# design.net
KiCad netlist of a schematic drawn in Altium Designer
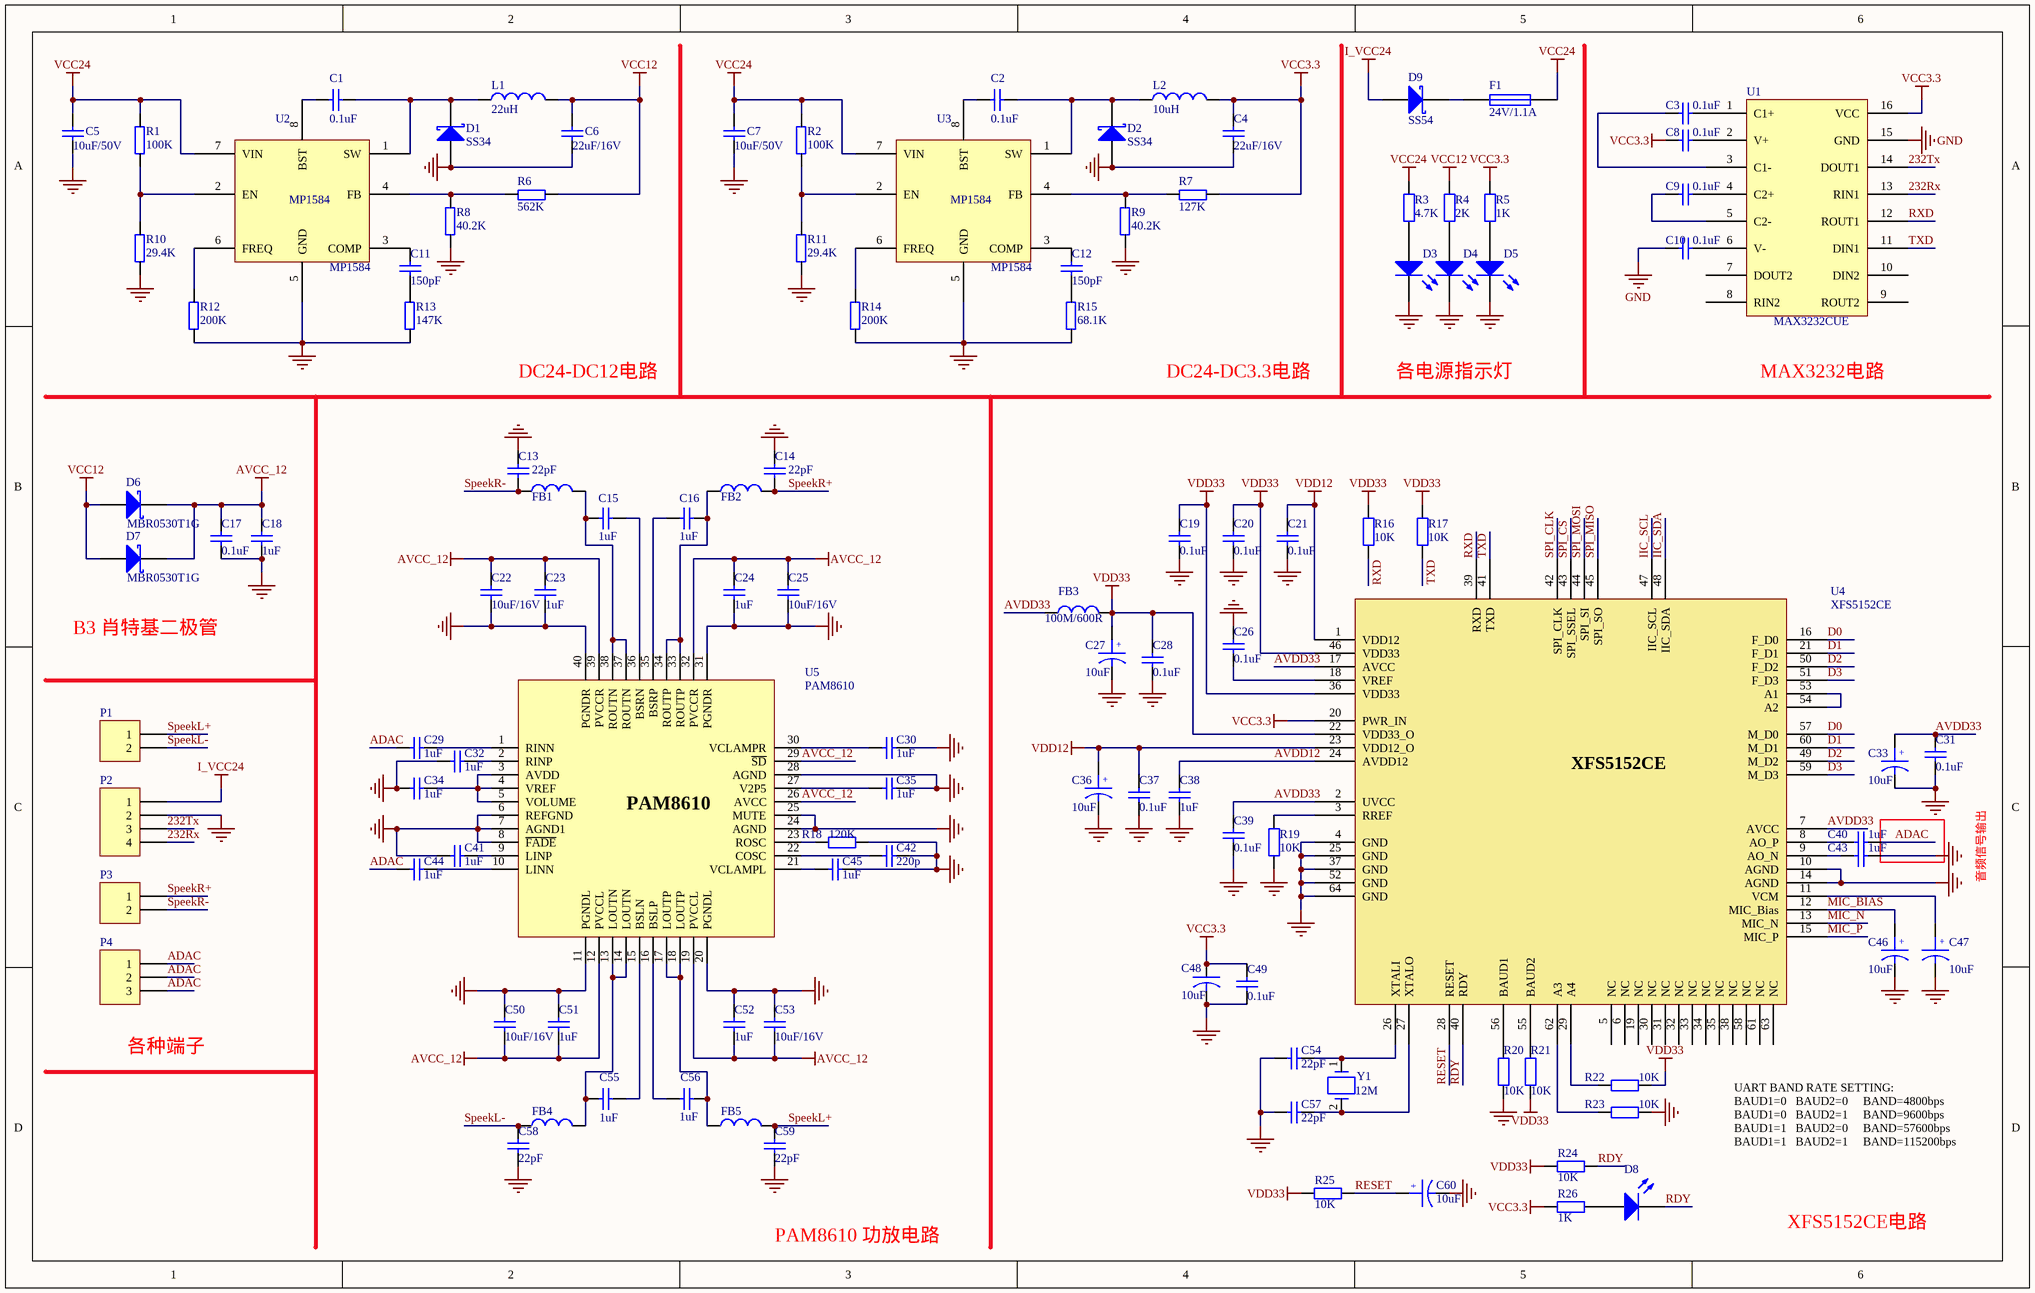
[diagram p0: 盟科大讯飞.SchDoc]

(export (version "E")
  (design (tool "Eeschema 10.0.6"))
  (components
    (comp (ref "C1")
      (value "0.1uF")
      (footprint "LC-0603_C")
      (description "Capacitor (Semiconductor SIM Model)")
      (fields (field (name "PUBLISHER") "Altium Limited"))
      (libsource (lib "Miscellaneous Devices") (part "Cap Semi"))
    )
    (comp (ref "C2")
      (value "0.1uF")
      (footprint "LC-0603_C")
      (description "Capacitor (Semiconductor SIM Model)")
      (fields (field (name "PUBLISHER") "Altium Limited"))
      (libsource (lib "Miscellaneous Devices") (part "Cap Semi"))
    )
    (comp (ref "C3")
      (value "0.1uF")
      (footprint "LC-0603_C")
      (description "Capacitor (Semiconductor SIM Model)")
      (fields (field (name "PUBLISHER") "Altium Limited"))
      (libsource (lib "Miscellaneous Devices") (part "Cap Semi"))
    )
    (comp (ref "C4")
      (value "22uF/16V")
      (footprint "LC-1206_C")
      (description "Capacitor (Semiconductor SIM Model)")
      (fields (field (name "PUBLISHER") "Altium Limited"))
      (libsource (lib "Miscellaneous Devices") (part "Cap Semi"))
    )
    (comp (ref "C5")
      (value "10uF/50V")
      (footprint "LC-1206_C")
      (description "Capacitor (Semiconductor SIM Model)")
      (fields (field (name "PUBLISHER") "Altium Limited"))
      (libsource (lib "Miscellaneous Devices") (part "Cap Semi"))
    )
    (comp (ref "C6")
      (value "22uF/16V")
      (footprint "LC-1206_C")
      (description "Capacitor (Semiconductor SIM Model)")
      (fields (field (name "PUBLISHER") "Altium Limited"))
      (libsource (lib "Miscellaneous Devices") (part "Cap Semi"))
    )
    (comp (ref "C7")
      (value "10uF/50V")
      (footprint "LC-1206_C")
      (description "Capacitor (Semiconductor SIM Model)")
      (fields (field (name "PUBLISHER") "Altium Limited"))
      (libsource (lib "Miscellaneous Devices") (part "Cap Semi"))
    )
    (comp (ref "C8")
      (value "0.1uF")
      (footprint "LC-0603_C")
      (description "Capacitor (Semiconductor SIM Model)")
      (fields (field (name "PUBLISHER") "Altium Limited"))
      (libsource (lib "Miscellaneous Devices") (part "Cap Semi"))
    )
    (comp (ref "C9")
      (value "0.1uF")
      (footprint "LC-0603_C")
      (description "Capacitor (Semiconductor SIM Model)")
      (fields (field (name "PUBLISHER") "Altium Limited"))
      (libsource (lib "Miscellaneous Devices") (part "Cap Semi"))
    )
    (comp (ref "C10")
      (value "0.1uF")
      (footprint "LC-0603_C")
      (description "Capacitor (Semiconductor SIM Model)")
      (fields (field (name "PUBLISHER") "Altium Limited"))
      (libsource (lib "Miscellaneous Devices") (part "Cap Semi"))
    )
    (comp (ref "C11")
      (value "150pF")
      (footprint "LC-0603_C")
      (description "Capacitor (Semiconductor SIM Model)")
      (fields (field (name "PUBLISHER") "Altium Limited"))
      (libsource (lib "Miscellaneous Devices") (part "Cap Semi"))
    )
    (comp (ref "C12")
      (value "150pF")
      (footprint "LC-0603_C")
      (description "Capacitor (Semiconductor SIM Model)")
      (fields (field (name "PUBLISHER") "Altium Limited"))
      (libsource (lib "Miscellaneous Devices") (part "Cap Semi"))
    )
    (comp (ref "C13")
      (value "22pF")
      (footprint "LC-0603_C")
      (description "Capacitor (Semiconductor SIM Model)")
      (fields (field (name "PUBLISHER") "Altium Limited"))
      (libsource (lib "Miscellaneous Devices") (part "Cap Semi"))
    )
    (comp (ref "C14")
      (value "22pF")
      (footprint "LC-0603_C")
      (description "Capacitor (Semiconductor SIM Model)")
      (fields (field (name "PUBLISHER") "Altium Limited"))
      (libsource (lib "Miscellaneous Devices") (part "Cap Semi"))
    )
    (comp (ref "C15")
      (value "1uF")
      (footprint "LC-0603_C")
      (description "Capacitor (Semiconductor SIM Model)")
      (fields (field (name "PUBLISHER") "Altium Limited"))
      (libsource (lib "Miscellaneous Devices") (part "Cap Semi"))
    )
    (comp (ref "C16")
      (value "1uF")
      (footprint "LC-0603_C")
      (description "Capacitor (Semiconductor SIM Model)")
      (fields (field (name "PUBLISHER") "Altium Limited"))
      (libsource (lib "Miscellaneous Devices") (part "Cap Semi"))
    )
    (comp (ref "C17")
      (value "0.1uF")
      (footprint "LC-0603_C")
      (description "Capacitor (Semiconductor SIM Model)")
      (fields (field (name "PUBLISHER") "Altium Limited"))
      (libsource (lib "Miscellaneous Devices") (part "Cap Semi"))
    )
    (comp (ref "C18")
      (value "1uF")
      (footprint "LC-0603_C")
      (description "Capacitor (Semiconductor SIM Model)")
      (fields (field (name "PUBLISHER") "Altium Limited"))
      (libsource (lib "Miscellaneous Devices") (part "Cap Semi"))
    )
    (comp (ref "C19")
      (value "0.1uF")
      (footprint "LC-0603_C")
      (description "Capacitor (Semiconductor SIM Model)")
      (fields (field (name "PUBLISHER") "Altium Limited"))
      (libsource (lib "Miscellaneous Devices") (part "Cap Semi"))
    )
    (comp (ref "C20")
      (value "0.1uF")
      (footprint "LC-0603_C")
      (description "Capacitor (Semiconductor SIM Model)")
      (fields (field (name "PUBLISHER") "Altium Limited"))
      (libsource (lib "Miscellaneous Devices") (part "Cap Semi"))
    )
    (comp (ref "C21")
      (value "0.1uF")
      (footprint "LC-0603_C")
      (description "Capacitor (Semiconductor SIM Model)")
      (fields (field (name "PUBLISHER") "Altium Limited"))
      (libsource (lib "Miscellaneous Devices") (part "Cap Semi"))
    )
    (comp (ref "C22")
      (value "10uF/16V")
      (footprint "LC-1206_C")
      (description "电容")
      (fields (field (name "PUBLISHER") "Altium Limited"))
      (libsource (lib "*") (part "Cap NP"))
    )
    (comp (ref "C23")
      (value "1uF")
      (footprint "LC-0603_C")
      (description "Capacitor (Semiconductor SIM Model)")
      (fields (field (name "PUBLISHER") "Altium Limited"))
      (libsource (lib "Miscellaneous Devices") (part "Cap Semi"))
    )
    (comp (ref "C24")
      (value "1uF")
      (footprint "LC-0603_C")
      (description "Capacitor (Semiconductor SIM Model)")
      (fields (field (name "PUBLISHER") "Altium Limited"))
      (libsource (lib "Miscellaneous Devices") (part "Cap Semi"))
    )
    (comp (ref "C25")
      (value "10uF/16V")
      (footprint "LC-1206_C")
      (description "电容")
      (fields (field (name "PUBLISHER") "Altium Limited"))
      (libsource (lib "*") (part "Cap NP"))
    )
    (comp (ref "C26")
      (value "0.1uF")
      (footprint "LC-0603_C")
      (description "Capacitor (Semiconductor SIM Model)")
      (fields (field (name "PUBLISHER") "Altium Limited"))
      (libsource (lib "Miscellaneous Devices") (part "Cap Semi"))
    )
    (comp (ref "C27") (value "10uF") (footprint "LC-CASE-A_3216") (libsource (lib "*") (part "CAP POL")))
    (comp (ref "C28")
      (value "0.1uF")
      (footprint "LC-0603_C")
      (description "Capacitor (Semiconductor SIM Model)")
      (fields (field (name "PUBLISHER") "Altium Limited"))
      (libsource (lib "Miscellaneous Devices") (part "Cap Semi"))
    )
    (comp (ref "C29")
      (value "1uF")
      (footprint "LC-0603_C")
      (description "Capacitor (Semiconductor SIM Model)")
      (fields (field (name "PUBLISHER") "Altium Limited"))
      (libsource (lib "Miscellaneous Devices") (part "Cap Semi"))
    )
    (comp (ref "C30")
      (value "1uF")
      (footprint "LC-0603_C")
      (description "Capacitor (Semiconductor SIM Model)")
      (fields (field (name "PUBLISHER") "Altium Limited"))
      (libsource (lib "Miscellaneous Devices") (part "Cap Semi"))
    )
    (comp (ref "C31")
      (value "0.1uF")
      (footprint "LC-0603_C")
      (description "Capacitor (Semiconductor SIM Model)")
      (fields (field (name "PUBLISHER") "Altium Limited"))
      (libsource (lib "Miscellaneous Devices") (part "Cap Semi"))
    )
    (comp (ref "C32")
      (value "1uF")
      (footprint "LC-0603_C")
      (description "Capacitor (Semiconductor SIM Model)")
      (fields (field (name "PUBLISHER") "Altium Limited"))
      (libsource (lib "Miscellaneous Devices") (part "Cap Semi"))
    )
    (comp (ref "C33") (value "10uF") (footprint "LC-CASE-A_3216") (libsource (lib "*") (part "CAP POL")))
    (comp (ref "C34")
      (value "1uF")
      (footprint "LC-0603_C")
      (description "Capacitor (Semiconductor SIM Model)")
      (fields (field (name "PUBLISHER") "Altium Limited"))
      (libsource (lib "Miscellaneous Devices") (part "Cap Semi"))
    )
    (comp (ref "C35")
      (value "1uF")
      (footprint "LC-0603_C")
      (description "Capacitor (Semiconductor SIM Model)")
      (fields (field (name "PUBLISHER") "Altium Limited"))
      (libsource (lib "Miscellaneous Devices") (part "Cap Semi"))
    )
    (comp (ref "C36") (value "10uF") (footprint "LC-CASE-A_3216") (libsource (lib "*") (part "CAP POL")))
    (comp (ref "C37")
      (value "0.1uF")
      (footprint "LC-0603_C")
      (description "Capacitor (Semiconductor SIM Model)")
      (fields (field (name "PUBLISHER") "Altium Limited"))
      (libsource (lib "Miscellaneous Devices") (part "Cap Semi"))
    )
    (comp (ref "C38")
      (value "1uF")
      (footprint "LC-0603_C")
      (description "Capacitor (Semiconductor SIM Model)")
      (fields (field (name "PUBLISHER") "Altium Limited"))
      (libsource (lib "Miscellaneous Devices") (part "Cap Semi"))
    )
    (comp (ref "C39")
      (value "0.1uF")
      (footprint "LC-0603_C")
      (description "Capacitor (Semiconductor SIM Model)")
      (fields (field (name "PUBLISHER") "Altium Limited"))
      (libsource (lib "Miscellaneous Devices") (part "Cap Semi"))
    )
    (comp (ref "C40")
      (value "1uF")
      (footprint "LC-0603_C")
      (description "Capacitor (Semiconductor SIM Model)")
      (fields (field (name "PUBLISHER") "Altium Limited"))
      (libsource (lib "Miscellaneous Devices") (part "Cap Semi"))
    )
    (comp (ref "C41")
      (value "1uF")
      (footprint "LC-0603_C")
      (description "Capacitor (Semiconductor SIM Model)")
      (fields (field (name "PUBLISHER") "Altium Limited"))
      (libsource (lib "Miscellaneous Devices") (part "Cap Semi"))
    )
    (comp (ref "C42")
      (value "220p")
      (footprint "LC-0603_C")
      (description "Capacitor (Semiconductor SIM Model)")
      (fields (field (name "PUBLISHER") "Altium Limited"))
      (libsource (lib "Miscellaneous Devices") (part "Cap Semi"))
    )
    (comp (ref "C43")
      (value "1uF")
      (footprint "LC-0603_C")
      (description "Capacitor (Semiconductor SIM Model)")
      (fields (field (name "PUBLISHER") "Altium Limited"))
      (libsource (lib "Miscellaneous Devices") (part "Cap Semi"))
    )
    (comp (ref "C44")
      (value "1uF")
      (footprint "LC-0603_C")
      (description "Capacitor (Semiconductor SIM Model)")
      (fields (field (name "PUBLISHER") "Altium Limited"))
      (libsource (lib "Miscellaneous Devices") (part "Cap Semi"))
    )
    (comp (ref "C45")
      (value "1uF")
      (footprint "LC-0603_C")
      (description "Capacitor (Semiconductor SIM Model)")
      (fields (field (name "PUBLISHER") "Altium Limited"))
      (libsource (lib "Miscellaneous Devices") (part "Cap Semi"))
    )
    (comp (ref "C46") (value "10uF") (footprint "LC-CASE-A_3216") (libsource (lib "*") (part "CAP POL")))
    (comp (ref "C47") (value "10uF") (footprint "LC-CASE-A_3216") (libsource (lib "*") (part "CAP POL")))
    (comp (ref "C48")
      (value "10uF")
      (footprint "LC-CASE-A_3216")
      (description "Capacitor")
      (libsource (lib "*") (part "CAPACITOR"))
    )
    (comp (ref "C49")
      (value "0.1uF")
      (footprint "LC-0603_C")
      (description "Capacitor (Semiconductor SIM Model)")
      (fields (field (name "PUBLISHER") "Altium Limited"))
      (libsource (lib "Miscellaneous Devices") (part "Cap Semi"))
    )
    (comp (ref "C50")
      (value "10uF/16V")
      (footprint "LC-1206_C")
      (description "电容")
      (fields (field (name "PUBLISHER") "Altium Limited"))
      (libsource (lib "*") (part "Cap NP"))
    )
    (comp (ref "C51")
      (value "1uF")
      (footprint "LC-0603_C")
      (description "Capacitor (Semiconductor SIM Model)")
      (fields (field (name "PUBLISHER") "Altium Limited"))
      (libsource (lib "Miscellaneous Devices") (part "Cap Semi"))
    )
    (comp (ref "C52")
      (value "1uF")
      (footprint "LC-0603_C")
      (description "Capacitor (Semiconductor SIM Model)")
      (fields (field (name "PUBLISHER") "Altium Limited"))
      (libsource (lib "Miscellaneous Devices") (part "Cap Semi"))
    )
    (comp (ref "C53")
      (value "10uF/16V")
      (footprint "LC-1206_C")
      (description "电容")
      (fields (field (name "PUBLISHER") "Altium Limited"))
      (libsource (lib "*") (part "Cap NP"))
    )
    (comp (ref "C54")
      (value "22pF")
      (footprint "LC-0603_C")
      (description "电容")
      (fields (field (name "PUBLISHER") "Altium Limited"))
      (libsource (lib "*") (part "Cap NP"))
    )
    (comp (ref "C55")
      (value "1uF")
      (footprint "LC-0603_C")
      (description "Capacitor (Semiconductor SIM Model)")
      (fields (field (name "PUBLISHER") "Altium Limited"))
      (libsource (lib "Miscellaneous Devices") (part "Cap Semi"))
    )
    (comp (ref "C56")
      (value "1uF")
      (footprint "LC-0603_C")
      (description "Capacitor (Semiconductor SIM Model)")
      (fields (field (name "PUBLISHER") "Altium Limited"))
      (libsource (lib "Miscellaneous Devices") (part "Cap Semi"))
    )
    (comp (ref "C57")
      (value "22pF")
      (footprint "LC-0603_C")
      (description "电容")
      (fields (field (name "PUBLISHER") "Altium Limited"))
      (libsource (lib "*") (part "Cap NP"))
    )
    (comp (ref "C58")
      (value "22pF")
      (footprint "LC-0603_C")
      (description "Capacitor (Semiconductor SIM Model)")
      (fields (field (name "PUBLISHER") "Altium Limited"))
      (libsource (lib "Miscellaneous Devices") (part "Cap Semi"))
    )
    (comp (ref "C59")
      (value "22pF")
      (footprint "LC-0603_C")
      (description "Capacitor (Semiconductor SIM Model)")
      (fields (field (name "PUBLISHER") "Altium Limited"))
      (libsource (lib "Miscellaneous Devices") (part "Cap Semi"))
    )
    (comp (ref "C60") (value "10uF") (footprint "LC-CASE-A_3216") (libsource (lib "*") (part "CAP POL")))
    (comp (ref "D1")
      (value "SS34")
      (footprint "SS34")
      (description "Schottky Rectifier")
      (fields (field (name "PUBLISHER") "Altium Limited"))
      (libsource (lib "Miscellaneous Devices") (part "Diode 18TQ045"))
    )
    (comp (ref "D2")
      (value "SS34")
      (footprint "SS34")
      (description "Schottky Rectifier")
      (fields (field (name "PUBLISHER") "Altium Limited"))
      (libsource (lib "Miscellaneous Devices") (part "Diode 18TQ045"))
    )
    (comp (ref "D3")
      (value "LED")
      (footprint "LC-0805_LED_S1")
      (description "Typical INFRARED GaAs LED")
      (fields (field (name "PUBLISHER") "Altium Limited"))
      (libsource (lib "Miscellaneous Devices") (part "LED0"))
    )
    (comp (ref "D4")
      (value "LED")
      (footprint "LC-0805_LED_S1")
      (description "Typical INFRARED GaAs LED")
      (fields (field (name "PUBLISHER") "Altium Limited"))
      (libsource (lib "Miscellaneous Devices") (part "LED0"))
    )
    (comp (ref "D5")
      (value "LED")
      (footprint "LC-0805_LED_S1")
      (description "Typical INFRARED GaAs LED")
      (fields (field (name "PUBLISHER") "Altium Limited"))
      (libsource (lib "Miscellaneous Devices") (part "LED0"))
    )
    (comp (ref "D6")
      (value "MBR0530T1G")
      (footprint "B3肖特基二极管")
      (description "Schottky Rectifier")
      (fields (field (name "PUBLISHER") "Altium Limited"))
      (libsource (lib "Miscellaneous Devices") (part "Diode 18TQ045"))
    )
    (comp (ref "D7")
      (value "MBR0530T1G")
      (footprint "B3肖特基二极管")
      (description "Schottky Rectifier")
      (fields (field (name "PUBLISHER") "Altium Limited"))
      (libsource (lib "Miscellaneous Devices") (part "Diode 18TQ045"))
    )
    (comp (ref "D8")
      (value "LED")
      (footprint "LC-0805_LED_S1")
      (description "Typical INFRARED GaAs LED")
      (fields (field (name "PUBLISHER") "Altium Limited"))
      (libsource (lib "Miscellaneous Devices") (part "LED0"))
    )
    (comp (ref "D9")
      (value "SS54")
      (footprint "DIOM6959X26N")
      (description "Schottky Rectifier")
      (fields (field (name "PUBLISHER") "Altium Limited"))
      (libsource (lib "Miscellaneous Devices") (part "Diode 18TQ045"))
    )
    (comp (ref "F1")
      (value "24V/1.1A")
      (footprint "1206 F")
      (description "Fuse")
      (fields (field (name "PUBLISHER") "Altium Limited"))
      (libsource (lib "Miscellaneous Devices") (part "Fuse 1"))
    )
    (comp (ref "FB1")
      (value "100M/600R")
      (footprint "LC-0805_L")
      (description "磁珠")
      (fields (field (name "PUBLISHER") "Altium Limited"))
      (libsource (lib "*") (part "Fbead"))
    )
    (comp (ref "FB2")
      (value "100M/600R")
      (footprint "LC-0805_L")
      (description "磁珠")
      (fields (field (name "PUBLISHER") "Altium Limited"))
      (libsource (lib "*") (part "Fbead"))
    )
    (comp (ref "FB3")
      (value "100M/600R")
      (footprint "LC-0805_L")
      (description "磁珠")
      (fields (field (name "PUBLISHER") "Altium Limited"))
      (libsource (lib "*") (part "Fbead"))
    )
    (comp (ref "FB4")
      (value "100M/600R")
      (footprint "LC-0805_L")
      (description "磁珠")
      (fields (field (name "PUBLISHER") "Altium Limited"))
      (libsource (lib "*") (part "Fbead"))
    )
    (comp (ref "FB5")
      (value "100M/600R")
      (footprint "LC-0805_L")
      (description "磁珠")
      (fields (field (name "PUBLISHER") "Altium Limited"))
      (libsource (lib "*") (part "Fbead"))
    )
    (comp (ref "L1")
      (value "22uH")
      (footprint "7*7*4mm电感")
      (description "Inductor")
      (fields (field (name "PUBLISHER") "Altium Limited"))
      (libsource (lib "Miscellaneous Devices") (part "Inductor"))
    )
    (comp (ref "L2")
      (value "10uH")
      (footprint "7*7*4mm电感")
      (description "Inductor")
      (fields (field (name "PUBLISHER") "Altium Limited"))
      (libsource (lib "Miscellaneous Devices") (part "Inductor"))
    )
    (comp (ref "P1")
      (value "~")
      (footprint "DZ-2-3.5mm")
      (description "Header, 2-Pin")
      (fields (field (name "PUBLISHER") "Altium Limited"))
      (libsource (lib "Miscellaneous Connectors") (part "Header 2"))
    )
    (comp (ref "P2")
      (value "~")
      (footprint "DZ-4-3.5mm")
      (description "Header, 4-Pin")
      (fields (field (name "PUBLISHER") "Altium Limited"))
      (libsource (lib "Miscellaneous Connectors") (part "Header 4"))
    )
    (comp (ref "P3")
      (value "~")
      (footprint "DZ-2-3.5mm")
      (description "Header, 2-Pin")
      (fields (field (name "PUBLISHER") "Altium Limited"))
      (libsource (lib "Miscellaneous Connectors") (part "Header 2"))
    )
    (comp (ref "P4")
      (value "~")
      (footprint "单刀双掷贴片开关")
      (description "Header, 3-Pin")
      (fields (field (name "PUBLISHER") "Altium Limited"))
      (libsource (lib "Miscellaneous Connectors") (part "Header 3"))
    )
    (comp (ref "R1")
      (value "100K")
      (footprint "LC-0603_R")
      (libsource (lib "Explorer STM32F407封装库") (part "R_2"))
    )
    (comp (ref "R2")
      (value "100K")
      (footprint "LC-0603_R")
      (libsource (lib "Explorer STM32F407封装库") (part "R_2"))
    )
    (comp (ref "R3")
      (value "4.7K")
      (footprint "LC-0603_R")
      (description "Resistor")
      (fields (field (name "PUBLISHER") "Altium Limited"))
      (libsource (lib "*") (part "Res2"))
    )
    (comp (ref "R4")
      (value "2K")
      (footprint "LC-0603_R")
      (description "Resistor")
      (fields (field (name "PUBLISHER") "Altium Limited"))
      (libsource (lib "") (part "Res2_3"))
    )
    (comp (ref "R5")
      (value "1K")
      (footprint "LC-0603_R")
      (description "Resistor")
      (fields (field (name "PUBLISHER") "Altium Limited"))
      (libsource (lib "*") (part "Res2"))
    )
    (comp (ref "R6")
      (value "562K")
      (footprint "LC-0603_R")
      (libsource (lib "Explorer STM32F407封装库") (part "R_2"))
    )
    (comp (ref "R7")
      (value "127K")
      (footprint "LC-0603_R")
      (libsource (lib "Explorer STM32F407封装库") (part "R_2"))
    )
    (comp (ref "R8")
      (value "40.2K")
      (footprint "LC-0603_R")
      (libsource (lib "Explorer STM32F407封装库") (part "R_2"))
    )
    (comp (ref "R9")
      (value "40.2K")
      (footprint "LC-0603_R")
      (libsource (lib "Explorer STM32F407封装库") (part "R_2"))
    )
    (comp (ref "R10")
      (value "29.4K")
      (footprint "LC-0603_R")
      (libsource (lib "Explorer STM32F407封装库") (part "R_2"))
    )
    (comp (ref "R11")
      (value "29.4K")
      (footprint "LC-0603_R")
      (libsource (lib "Explorer STM32F407封装库") (part "R_2"))
    )
    (comp (ref "R12")
      (value "200K")
      (footprint "LC-0603_R")
      (libsource (lib "Explorer STM32F407封装库") (part "R_2"))
    )
    (comp (ref "R13")
      (value "147K")
      (footprint "LC-0603_R")
      (libsource (lib "Explorer STM32F407封装库") (part "R_2"))
    )
    (comp (ref "R14")
      (value "200K")
      (footprint "LC-0603_R")
      (libsource (lib "Explorer STM32F407封装库") (part "R_2"))
    )
    (comp (ref "R15")
      (value "68.1K")
      (footprint "LC-0603_R")
      (libsource (lib "Explorer STM32F407封装库") (part "R_2"))
    )
    (comp (ref "R16")
      (value "10K")
      (footprint "LC-0603_R")
      (description "Resistor")
      (fields (field (name "PUBLISHER") "Altium Limited"))
      (libsource (lib "") (part "Res2_3"))
    )
    (comp (ref "R17")
      (value "10K")
      (footprint "LC-0603_R")
      (description "Resistor")
      (fields (field (name "PUBLISHER") "Altium Limited"))
      (libsource (lib "*") (part "Res2"))
    )
    (comp (ref "R18")
      (value "120K")
      (footprint "LC-0603_R")
      (description "Resistor")
      (fields (field (name "PUBLISHER") "Altium Limited"))
      (libsource (lib "") (part "Res2_2"))
    )
    (comp (ref "R19")
      (value "10K")
      (footprint "LC-0603_R")
      (description "Resistor")
      (fields (field (name "PUBLISHER") "Altium Limited"))
      (libsource (lib "") (part "Res2_3"))
    )
    (comp (ref "R20")
      (value "10K")
      (footprint "LC-0603_R")
      (description "Resistor")
      (fields (field (name "PUBLISHER") "Altium Limited"))
      (libsource (lib "*") (part "Res2"))
    )
    (comp (ref "R21")
      (value "10K")
      (footprint "LC-0603_R")
      (description "Resistor")
      (fields (field (name "PUBLISHER") "Altium Limited"))
      (libsource (lib "*") (part "Res2"))
    )
    (comp (ref "R22")
      (value "10K")
      (footprint "LC-0603_R")
      (description "Resistor")
      (fields (field (name "PUBLISHER") "Altium Limited"))
      (libsource (lib "") (part "Res2_1"))
    )
    (comp (ref "R23")
      (value "10K")
      (footprint "LC-0603_R")
      (description "Resistor")
      (fields (field (name "PUBLISHER") "Altium Limited"))
      (libsource (lib "") (part "Res2_2"))
    )
    (comp (ref "R24")
      (value "10K")
      (footprint "LC-0603_R")
      (description "Resistor")
      (fields (field (name "PUBLISHER") "Altium Limited"))
      (libsource (lib "") (part "Res2_1"))
    )
    (comp (ref "R25")
      (value "10K")
      (footprint "LC-0603_R")
      (description "Resistor")
      (fields (field (name "PUBLISHER") "Altium Limited"))
      (libsource (lib "") (part "Res2_1"))
    )
    (comp (ref "R26")
      (value "1K")
      (footprint "LC-0603_R")
      (description "Resistor")
      (fields (field (name "PUBLISHER") "Altium Limited"))
      (libsource (lib "") (part "Res2_1"))
    )
    (comp (ref "U1")
      (value "MAX3232CUE")
      (footprint "LC-SOIC-16_150mil")
      (libsource (lib "Smart_board_v1") (part "MAX3232CUE"))
    )
    (comp (ref "U2")
      (value "MP1584")
      (footprint "LC-SOIC-8_EP_150mil")
      (libsource (lib "磁导航") (part "MP1584EN"))
    )
    (comp (ref "U3")
      (value "MP1584")
      (footprint "LC-SOIC-8_EP_150mil")
      (libsource (lib "磁导航") (part "MP1584EN"))
    )
    (comp (ref "U4") (value "XFS5152CE") (footprint "LQFP64 10*10") (libsource (lib "*") (part "XFS5152-2")))
    (comp (ref "U5")
      (value "PAM8610")
      (footprint "QFN50P600X600X80-40N")
      (libsource (lib "my third") (part "PAM8610功放芯片"))
    )
    (comp (ref "Y1")
      (value "12M")
      (footprint "XTAL 晶振")
      (description "晶振")
      (libsource (lib "*") (part "XTAL1"))
    )
  )
  (nets
    (net (code "1") (name "/232Rx") (class "Default")
      (node (ref "P2") (pin "4") (pinfunction "4_4") (pintype "passive"))
      (node (ref "U1") (pin "13") (pinfunction "RIN1_13") (pintype "passive"))
    )
    (net (code "2") (name "/232Tx") (class "Default")
      (node (ref "P2") (pin "3") (pinfunction "3_3") (pintype "passive"))
      (node (ref "U1") (pin "14") (pinfunction "DOUT1_14") (pintype "passive"))
    )
    (net (code "3") (name "/ADAC") (class "Default")
      (node (ref "C29") (pin "1") (pinfunction "1_1") (pintype "passive"))
      (node (ref "C40") (pin "1") (pinfunction "1_1") (pintype "passive"))
      (node (ref "C44") (pin "1") (pinfunction "1_1") (pintype "passive"))
      (node (ref "P4") (pin "1") (pinfunction "1_1") (pintype "passive"))
      (node (ref "P4") (pin "2") (pinfunction "2_2") (pintype "passive"))
      (node (ref "P4") (pin "3") (pinfunction "3_3") (pintype "passive"))
    )
    (net (code "4") (name "/AVDD12") (class "Default")
      (node (ref "C38") (pin "2") (pinfunction "2_2") (pintype "passive"))
      (node (ref "U4") (pin "24") (pinfunction "AVDD12_24") (pintype "passive"))
    )
    (net (code "5") (name "/AVDD33") (class "Default")
      (node (ref "C31") (pin "1") (pinfunction "1_1") (pintype "passive"))
      (node (ref "C33") (pin "1") (pinfunction "1_1") (pintype "passive"))
      (node (ref "C39") (pin "1") (pinfunction "1_1") (pintype "passive"))
      (node (ref "FB3") (pin "1") (pinfunction "1_1") (pintype "passive"))
      (node (ref "U4") (pin "17") (pinfunction "AVCC_17") (pintype "passive"))
      (node (ref "U4") (pin "2") (pinfunction "UVCC_2") (pintype "passive"))
      (node (ref "U4") (pin "7") (pinfunction "AVCC_7") (pintype "passive"))
    )
    (net (code "6") (name "/D0") (class "Default")
      (node (ref "U4") (pin "16") (pinfunction "F_D0_16") (pintype "passive"))
      (node (ref "U4") (pin "57") (pinfunction "M_D0_57") (pintype "passive"))
    )
    (net (code "7") (name "/D1") (class "Default")
      (node (ref "U4") (pin "21") (pinfunction "F_D1_21") (pintype "passive"))
      (node (ref "U4") (pin "60") (pinfunction "M_D1_60") (pintype "passive"))
    )
    (net (code "8") (name "/D2") (class "Default")
      (node (ref "U4") (pin "49") (pinfunction "M_D2_49") (pintype "passive"))
      (node (ref "U4") (pin "50") (pinfunction "F_D2_50") (pintype "passive"))
    )
    (net (code "9") (name "/D3") (class "Default")
      (node (ref "U4") (pin "51") (pinfunction "F_D3_51") (pintype "passive"))
      (node (ref "U4") (pin "59") (pinfunction "M_D3_59") (pintype "passive"))
    )
    (net (code "10") (name "/IIC_SCL") (class "Default")
      (node (ref "U4") (pin "47") (pinfunction "IIC_SCL_47") (pintype "passive"))
    )
    (net (code "11") (name "/IIC_SDA") (class "Default")
      (node (ref "U4") (pin "48") (pinfunction "IIC_SDA_48") (pintype "passive"))
    )
    (net (code "12") (name "/MIC_BIAS") (class "Default")
      (node (ref "C46") (pin "1") (pinfunction "1_1") (pintype "passive"))
      (node (ref "U4") (pin "12") (pinfunction "MIC_Bias_12") (pintype "passive"))
    )
    (net (code "13") (name "/MIC_N") (class "Default")
      (node (ref "U4") (pin "13") (pinfunction "MIC_N_13") (pintype "passive"))
    )
    (net (code "14") (name "/MIC_P") (class "Default")
      (node (ref "U4") (pin "15") (pinfunction "MIC_P_15") (pintype "passive"))
    )
    (net (code "15") (name "/RDY") (class "Default")
      (node (ref "D8") (pin "2") (pinfunction "K_2") (pintype "passive"))
      (node (ref "R24") (pin "2") (pinfunction "2_2") (pintype "passive"))
      (node (ref "U4") (pin "40") (pinfunction "RDY_40") (pintype "passive"))
    )
    (net (code "16") (name "/RESET") (class "Default")
      (node (ref "C60") (pin "1") (pinfunction "1_1") (pintype "passive"))
      (node (ref "R25") (pin "2") (pinfunction "2_2") (pintype "passive"))
      (node (ref "U4") (pin "28") (pinfunction "RESET_28") (pintype "passive"))
    )
    (net (code "17") (name "/RXD") (class "Default")
      (node (ref "R16") (pin "1") (pinfunction "1_1") (pintype "passive"))
      (node (ref "U1") (pin "12") (pinfunction "ROUT1_12") (pintype "passive"))
      (node (ref "U4") (pin "39") (pinfunction "RXD_39") (pintype "passive"))
    )
    (net (code "18") (name "/SPI_CLK") (class "Default")
      (node (ref "U4") (pin "42") (pinfunction "SPI_CLK_42") (pintype "passive"))
    )
    (net (code "19") (name "/SPI_CS") (class "Default")
      (node (ref "U4") (pin "43") (pinfunction "SPI_SSEL_43") (pintype "passive"))
    )
    (net (code "20") (name "/SPI_MISO") (class "Default")
      (node (ref "U4") (pin "45") (pinfunction "SPI_SO_45") (pintype "passive"))
    )
    (net (code "21") (name "/SPI_MOSI") (class "Default")
      (node (ref "U4") (pin "44") (pinfunction "SPI_SI_44") (pintype "passive"))
    )
    (net (code "22") (name "/SpeekL+") (class "Default")
      (node (ref "C59") (pin "2") (pinfunction "2_2") (pintype "passive"))
      (node (ref "FB5") (pin "2") (pinfunction "2_2") (pintype "passive"))
      (node (ref "P1") (pin "1") (pinfunction "1_1") (pintype "passive"))
    )
    (net (code "23") (name "/SpeekL-") (class "Default")
      (node (ref "C58") (pin "2") (pinfunction "2_2") (pintype "passive"))
      (node (ref "FB4") (pin "1") (pinfunction "1_1") (pintype "passive"))
      (node (ref "P1") (pin "2") (pinfunction "2_2") (pintype "passive"))
    )
    (net (code "24") (name "/SpeekR+") (class "Default")
      (node (ref "C14") (pin "2") (pinfunction "2_2") (pintype "passive"))
      (node (ref "FB2") (pin "2") (pinfunction "2_2") (pintype "passive"))
      (node (ref "P3") (pin "1") (pinfunction "1_1") (pintype "passive"))
    )
    (net (code "25") (name "/SpeekR-") (class "Default")
      (node (ref "C13") (pin "2") (pinfunction "2_2") (pintype "passive"))
      (node (ref "FB1") (pin "1") (pinfunction "1_1") (pintype "passive"))
      (node (ref "P3") (pin "2") (pinfunction "2_2") (pintype "passive"))
    )
    (net (code "26") (name "/TXD") (class "Default")
      (node (ref "R17") (pin "2") (pinfunction "2_2") (pintype "passive"))
      (node (ref "U1") (pin "11") (pinfunction "DIN1_11") (pintype "passive"))
      (node (ref "U4") (pin "41") (pinfunction "TXD_41") (pintype "passive"))
    )
    (net (code "27") (name "AVCC_12") (class "Default")
      (node (ref "C17") (pin "1") (pinfunction "1_1") (pintype "passive"))
      (node (ref "C18") (pin "1") (pinfunction "1_1") (pintype "passive"))
      (node (ref "C22") (pin "1") (pinfunction "1_1") (pintype "passive"))
      (node (ref "C23") (pin "1") (pinfunction "1_1") (pintype "passive"))
      (node (ref "C24") (pin "1") (pinfunction "1_1") (pintype "passive"))
      (node (ref "C25") (pin "1") (pinfunction "1_1") (pintype "passive"))
      (node (ref "C50") (pin "1") (pinfunction "1_1") (pintype "passive"))
      (node (ref "C51") (pin "1") (pinfunction "1_1") (pintype "passive"))
      (node (ref "C52") (pin "1") (pinfunction "1_1") (pintype "passive"))
      (node (ref "C53") (pin "1") (pinfunction "1_1") (pintype "passive"))
      (node (ref "D6") (pin "1") (pinfunction "K_1") (pintype "passive"))
      (node (ref "D7") (pin "1") (pinfunction "K_1") (pintype "passive"))
      (node (ref "U5") (pin "12") (pinfunction "PVCCL_12") (pintype "passive"))
      (node (ref "U5") (pin "19") (pinfunction "PVCCL_19") (pintype "passive"))
      (node (ref "U5") (pin "26") (pinfunction "AVCC_26") (pintype "passive"))
      (node (ref "U5") (pin "29") (pinfunction "~{SD}_29") (pintype "passive"))
      (node (ref "U5") (pin "32") (pinfunction "PVCCR_32") (pintype "passive"))
      (node (ref "U5") (pin "39") (pinfunction "PVCCR_39") (pintype "passive"))
    )
    (net (code "28") (name "GND") (class "Default")
      (node (ref "C10") (pin "2") (pinfunction "2_2") (pintype "passive"))
      (node (ref "C13") (pin "1") (pinfunction "1_1") (pintype "passive"))
      (node (ref "C14") (pin "1") (pinfunction "1_1") (pintype "passive"))
      (node (ref "C17") (pin "2") (pinfunction "2_2") (pintype "passive"))
      (node (ref "C18") (pin "2") (pinfunction "2_2") (pintype "passive"))
      (node (ref "C19") (pin "2") (pinfunction "2_2") (pintype "passive"))
      (node (ref "C20") (pin "2") (pinfunction "2_2") (pintype "passive"))
      (node (ref "C21") (pin "2") (pinfunction "2_2") (pintype "passive"))
      (node (ref "C22") (pin "2") (pinfunction "2_2") (pintype "passive"))
      (node (ref "C23") (pin "2") (pinfunction "2_2") (pintype "passive"))
      (node (ref "C24") (pin "2") (pinfunction "2_2") (pintype "passive"))
      (node (ref "C25") (pin "2") (pinfunction "2_2") (pintype "passive"))
      (node (ref "C26") (pin "1") (pinfunction "1_1") (pintype "passive"))
      (node (ref "C27") (pin "2") (pinfunction "2_2") (pintype "passive"))
      (node (ref "C28") (pin "2") (pinfunction "2_2") (pintype "passive"))
      (node (ref "C30") (pin "2") (pinfunction "2_2") (pintype "passive"))
      (node (ref "C31") (pin "2") (pinfunction "2_2") (pintype "passive"))
      (node (ref "C32") (pin "1") (pinfunction "1_1") (pintype "passive"))
      (node (ref "C33") (pin "2") (pinfunction "2_2") (pintype "passive"))
      (node (ref "C34") (pin "1") (pinfunction "1_1") (pintype "passive"))
      (node (ref "C35") (pin "2") (pinfunction "2_2") (pintype "passive"))
      (node (ref "C36") (pin "2") (pinfunction "2_2") (pintype "passive"))
      (node (ref "C37") (pin "2") (pinfunction "2_2") (pintype "passive"))
      (node (ref "C38") (pin "1") (pinfunction "1_1") (pintype "passive"))
      (node (ref "C39") (pin "2") (pinfunction "2_2") (pintype "passive"))
      (node (ref "C4") (pin "1") (pinfunction "1_1") (pintype "passive"))
      (node (ref "C41") (pin "1") (pinfunction "1_1") (pintype "passive"))
      (node (ref "C42") (pin "2") (pinfunction "2_2") (pintype "passive"))
      (node (ref "C43") (pin "1") (pinfunction "1_1") (pintype "passive"))
      (node (ref "C45") (pin "2") (pinfunction "2_2") (pintype "passive"))
      (node (ref "C46") (pin "2") (pinfunction "2_2") (pintype "passive"))
      (node (ref "C47") (pin "2") (pinfunction "2_2") (pintype "passive"))
      (node (ref "C48") (pin "2") (pinfunction "2_2") (pintype "passive"))
      (node (ref "C49") (pin "2") (pinfunction "2_2") (pintype "passive"))
      (node (ref "C5") (pin "2") (pinfunction "2_2") (pintype "passive"))
      (node (ref "C50") (pin "2") (pinfunction "2_2") (pintype "passive"))
      (node (ref "C51") (pin "2") (pinfunction "2_2") (pintype "passive"))
      (node (ref "C52") (pin "2") (pinfunction "2_2") (pintype "passive"))
      (node (ref "C53") (pin "2") (pinfunction "2_2") (pintype "passive"))
      (node (ref "C54") (pin "1") (pinfunction "1_1") (pintype "passive"))
      (node (ref "C57") (pin "1") (pinfunction "1_1") (pintype "passive"))
      (node (ref "C58") (pin "1") (pinfunction "1_1") (pintype "passive"))
      (node (ref "C59") (pin "1") (pinfunction "1_1") (pintype "passive"))
      (node (ref "C6") (pin "1") (pinfunction "1_1") (pintype "passive"))
      (node (ref "C60") (pin "2") (pinfunction "2_2") (pintype "passive"))
      (node (ref "C7") (pin "2") (pinfunction "2_2") (pintype "passive"))
      (node (ref "D1") (pin "2") (pinfunction "A_2") (pintype "passive"))
      (node (ref "D2") (pin "2") (pinfunction "A_2") (pintype "passive"))
      (node (ref "D3") (pin "2") (pinfunction "K_2") (pintype "passive"))
      (node (ref "D4") (pin "2") (pinfunction "K_2") (pintype "passive"))
      (node (ref "D5") (pin "2") (pinfunction "K_2") (pintype "passive"))
      (node (ref "P2") (pin "2") (pinfunction "2_2") (pintype "passive"))
      (node (ref "R10") (pin "2") (pintype "passive"))
      (node (ref "R11") (pin "2") (pintype "passive"))
      (node (ref "R12") (pin "2") (pintype "passive"))
      (node (ref "R13") (pin "2") (pintype "passive"))
      (node (ref "R14") (pin "2") (pintype "passive"))
      (node (ref "R15") (pin "2") (pintype "passive"))
      (node (ref "R18") (pin "1") (pinfunction "1_1") (pintype "passive"))
      (node (ref "R19") (pin "1") (pinfunction "1_1") (pintype "passive"))
      (node (ref "R20") (pin "2") (pinfunction "2_2") (pintype "passive"))
      (node (ref "R23") (pin "1") (pinfunction "1_1") (pintype "passive"))
      (node (ref "R8") (pin "2") (pintype "passive"))
      (node (ref "R9") (pin "2") (pintype "passive"))
      (node (ref "U1") (pin "15") (pinfunction "GND_15") (pintype "passive"))
      (node (ref "U2") (pin "5") (pinfunction "GND_5") (pintype "passive"))
      (node (ref "U3") (pin "5") (pinfunction "GND_5") (pintype "passive"))
      (node (ref "U4") (pin "10") (pinfunction "AGND_10") (pintype "passive"))
      (node (ref "U4") (pin "14") (pinfunction "AGND_14") (pintype "passive"))
      (node (ref "U4") (pin "25") (pinfunction "GND_25") (pintype "passive"))
      (node (ref "U4") (pin "37") (pinfunction "GND_37") (pintype "passive"))
      (node (ref "U4") (pin "4") (pinfunction "GND_4") (pintype "passive"))
      (node (ref "U4") (pin "52") (pinfunction "GND_52") (pintype "passive"))
      (node (ref "U4") (pin "64") (pinfunction "GND_64") (pintype "passive"))
      (node (ref "U5") (pin "11") (pinfunction "PGNDL_11") (pintype "passive"))
      (node (ref "U5") (pin "20") (pinfunction "PGNDL_20") (pintype "passive"))
      (node (ref "U5") (pin "24") (pinfunction "AGND_24") (pintype "passive"))
      (node (ref "U5") (pin "25") (pinfunction "MUTE_25") (pintype "passive"))
      (node (ref "U5") (pin "28") (pinfunction "AGND_28") (pintype "passive"))
      (node (ref "U5") (pin "31") (pinfunction "PGNDR_31") (pintype "passive"))
      (node (ref "U5") (pin "40") (pinfunction "PGNDR_40") (pintype "passive"))
      (node (ref "U5") (pin "6") (pinfunction "REFGND_6") (pintype "passive"))
      (node (ref "U5") (pin "7") (pinfunction "AGND1_7") (pintype "passive"))
      (node (ref "U5") (pin "8") (pinfunction "~{FADE}_8") (pintype "passive"))
    )
    (net (code "29") (name "I_VCC24") (class "Default")
      (node (ref "D9") (pin "2") (pinfunction "A_2") (pintype "passive"))
      (node (ref "P2") (pin "1") (pinfunction "1_1") (pintype "passive"))
    )
    (net (code "30") (name "Net-(C11-Pad1)") (class "Default")
      (node (ref "C11") (pin "1") (pinfunction "1_1") (pintype "passive"))
      (node (ref "R13") (pin "1") (pintype "passive"))
    )
    (net (code "31") (name "Net-(C12-Pad1)") (class "Default")
      (node (ref "C12") (pin "1") (pinfunction "1_1") (pintype "passive"))
      (node (ref "R15") (pin "1") (pintype "passive"))
    )
    (net (code "32") (name "Net-(C15-Pad1)") (class "Default")
      (node (ref "C15") (pin "1") (pinfunction "1_1") (pintype "passive"))
      (node (ref "FB1") (pin "2") (pinfunction "2_2") (pintype "passive"))
      (node (ref "U5") (pin "37") (pinfunction "ROUTN_37") (pintype "passive"))
      (node (ref "U5") (pin "38") (pinfunction "ROUTN_38") (pintype "passive"))
    )
    (net (code "33") (name "Net-(C16-Pad2)") (class "Default")
      (node (ref "C16") (pin "2") (pinfunction "2_2") (pintype "passive"))
      (node (ref "FB2") (pin "1") (pinfunction "1_1") (pintype "passive"))
      (node (ref "U5") (pin "33") (pinfunction "ROUTP_33") (pintype "passive"))
      (node (ref "U5") (pin "34") (pinfunction "ROUTP_34") (pintype "passive"))
    )
    (net (code "34") (name "Net-(C55-Pad2)") (class "Default")
      (node (ref "C55") (pin "2") (pinfunction "2_2") (pintype "passive"))
      (node (ref "FB4") (pin "2") (pinfunction "2_2") (pintype "passive"))
      (node (ref "U5") (pin "13") (pinfunction "LOUTN_13") (pintype "passive"))
      (node (ref "U5") (pin "14") (pinfunction "LOUTN_14") (pintype "passive"))
    )
    (net (code "35") (name "Net-(C56-Pad2)") (class "Default")
      (node (ref "C56") (pin "2") (pinfunction "2_2") (pintype "passive"))
      (node (ref "FB5") (pin "1") (pinfunction "1_1") (pintype "passive"))
      (node (ref "U5") (pin "17") (pinfunction "LOUTP_17") (pintype "passive"))
      (node (ref "U5") (pin "18") (pinfunction "LOUTP_18") (pintype "passive"))
    )
    (net (code "36") (name "Net-(D1-K)") (class "Default")
      (node (ref "C1") (pin "1") (pinfunction "1_1") (pintype "passive"))
      (node (ref "D1") (pin "1") (pinfunction "K_1") (pintype "passive"))
      (node (ref "L1") (pin "1") (pinfunction "1_1") (pintype "passive"))
      (node (ref "U2") (pin "1") (pinfunction "SW_1") (pintype "passive"))
    )
    (net (code "37") (name "Net-(D2-K)") (class "Default")
      (node (ref "C2") (pin "1") (pinfunction "1_1") (pintype "passive"))
      (node (ref "D2") (pin "1") (pinfunction "K_1") (pintype "passive"))
      (node (ref "L2") (pin "1") (pinfunction "1_1") (pintype "passive"))
      (node (ref "U3") (pin "1") (pinfunction "SW_1") (pintype "passive"))
    )
    (net (code "38") (name "Net-(D3-A)") (class "Default")
      (node (ref "D3") (pin "1") (pinfunction "A_1") (pintype "passive"))
      (node (ref "R3") (pin "2") (pinfunction "2_2") (pintype "passive"))
    )
    (net (code "39") (name "Net-(D4-A)") (class "Default")
      (node (ref "D4") (pin "1") (pinfunction "A_1") (pintype "passive"))
      (node (ref "R4") (pin "1") (pinfunction "1_1") (pintype "passive"))
    )
    (net (code "40") (name "Net-(D5-A)") (class "Default")
      (node (ref "D5") (pin "1") (pinfunction "A_1") (pintype "passive"))
      (node (ref "R5") (pin "2") (pinfunction "2_2") (pintype "passive"))
    )
    (net (code "41") (name "Net-(D8-A)") (class "Default")
      (node (ref "D8") (pin "1") (pinfunction "A_1") (pintype "passive"))
      (node (ref "R26") (pin "2") (pinfunction "2_2") (pintype "passive"))
    )
    (net (code "42") (name "Net-(D9-K)") (class "Default")
      (node (ref "D9") (pin "1") (pinfunction "K_1") (pintype "passive"))
      (node (ref "F1") (pin "1") (pinfunction "1_1") (pintype "passive"))
    )
    (net (code "43") (name "Net-(U1-C1+)") (class "Default")
      (node (ref "C3") (pin "1") (pinfunction "1_1") (pintype "passive"))
      (node (ref "U1") (pin "1") (pinfunction "C1+_1") (pintype "passive"))
    )
    (net (code "44") (name "Net-(U1-C1-)") (class "Default")
      (node (ref "C3") (pin "2") (pinfunction "2_2") (pintype "passive"))
      (node (ref "U1") (pin "3") (pinfunction "C1-_3") (pintype "passive"))
    )
    (net (code "45") (name "Net-(U1-C2+)") (class "Default")
      (node (ref "C9") (pin "1") (pinfunction "1_1") (pintype "passive"))
      (node (ref "U1") (pin "4") (pinfunction "C2+_4") (pintype "passive"))
    )
    (net (code "46") (name "Net-(U1-C2-)") (class "Default")
      (node (ref "C9") (pin "2") (pinfunction "2_2") (pintype "passive"))
      (node (ref "U1") (pin "5") (pinfunction "C2-_5") (pintype "passive"))
    )
    (net (code "47") (name "Net-(U1-V+)") (class "Default")
      (node (ref "C8") (pin "1") (pinfunction "1_1") (pintype "passive"))
      (node (ref "U1") (pin "2") (pinfunction "V+_2") (pintype "passive"))
    )
    (net (code "48") (name "Net-(U1-V-)") (class "Default")
      (node (ref "C10") (pin "1") (pinfunction "1_1") (pintype "passive"))
      (node (ref "U1") (pin "6") (pinfunction "V-_6") (pintype "passive"))
    )
    (net (code "49") (name "Net-(U2-BST)") (class "Default")
      (node (ref "C1") (pin "2") (pinfunction "2_2") (pintype "passive"))
      (node (ref "U2") (pin "8") (pinfunction "BST_8") (pintype "passive"))
    )
    (net (code "50") (name "Net-(U2-COMP)") (class "Default")
      (node (ref "C11") (pin "2") (pinfunction "2_2") (pintype "passive"))
      (node (ref "U2") (pin "3") (pinfunction "COMP_3") (pintype "passive"))
    )
    (net (code "51") (name "Net-(U2-EN)") (class "Default")
      (node (ref "R1") (pin "2") (pintype "passive"))
      (node (ref "R10") (pin "1") (pintype "passive"))
      (node (ref "U2") (pin "2") (pinfunction "EN_2") (pintype "passive"))
    )
    (net (code "52") (name "Net-(U2-FB)") (class "Default")
      (node (ref "R6") (pin "1") (pintype "passive"))
      (node (ref "R8") (pin "1") (pintype "passive"))
      (node (ref "U2") (pin "4") (pinfunction "FB_4") (pintype "passive"))
    )
    (net (code "53") (name "Net-(U2-FREQ)") (class "Default")
      (node (ref "R12") (pin "1") (pintype "passive"))
      (node (ref "U2") (pin "6") (pinfunction "FREQ_6") (pintype "passive"))
    )
    (net (code "54") (name "Net-(U3-BST)") (class "Default")
      (node (ref "C2") (pin "2") (pinfunction "2_2") (pintype "passive"))
      (node (ref "U3") (pin "8") (pinfunction "BST_8") (pintype "passive"))
    )
    (net (code "55") (name "Net-(U3-COMP)") (class "Default")
      (node (ref "C12") (pin "2") (pinfunction "2_2") (pintype "passive"))
      (node (ref "U3") (pin "3") (pinfunction "COMP_3") (pintype "passive"))
    )
    (net (code "56") (name "Net-(U3-EN)") (class "Default")
      (node (ref "R11") (pin "1") (pintype "passive"))
      (node (ref "R2") (pin "2") (pintype "passive"))
      (node (ref "U3") (pin "2") (pinfunction "EN_2") (pintype "passive"))
    )
    (net (code "57") (name "Net-(U3-FB)") (class "Default")
      (node (ref "R7") (pin "1") (pintype "passive"))
      (node (ref "R9") (pin "1") (pintype "passive"))
      (node (ref "U3") (pin "4") (pinfunction "FB_4") (pintype "passive"))
    )
    (net (code "58") (name "Net-(U3-FREQ)") (class "Default")
      (node (ref "R14") (pin "1") (pintype "passive"))
      (node (ref "U3") (pin "6") (pinfunction "FREQ_6") (pintype "passive"))
    )
    (net (code "59") (name "Net-(U4-A1)") (class "Default")
      (node (ref "U4") (pin "53") (pinfunction "A1_53") (pintype "passive"))
      (node (ref "U4") (pin "54") (pinfunction "A2_54") (pintype "passive"))
    )
    (net (code "60") (name "Net-(U4-A3)") (class "Default")
      (node (ref "R23") (pin "2") (pinfunction "2_2") (pintype "passive"))
      (node (ref "U4") (pin "62") (pinfunction "A3_62") (pintype "passive"))
    )
    (net (code "61") (name "Net-(U4-A4)") (class "Default")
      (node (ref "R22") (pin "1") (pinfunction "1_1") (pintype "passive"))
      (node (ref "U4") (pin "29") (pinfunction "A4_29") (pintype "passive"))
    )
    (net (code "62") (name "Net-(U4-AO_N)") (class "Default")
      (node (ref "C43") (pin "2") (pinfunction "2_2") (pintype "passive"))
      (node (ref "U4") (pin "9") (pinfunction "AO_N_9") (pintype "passive"))
    )
    (net (code "63") (name "Net-(U4-AO_P)") (class "Default")
      (node (ref "C40") (pin "2") (pinfunction "2_2") (pintype "passive"))
      (node (ref "U4") (pin "8") (pinfunction "AO_P_8") (pintype "passive"))
    )
    (net (code "64") (name "Net-(U4-BAUD1)") (class "Default")
      (node (ref "R20") (pin "1") (pinfunction "1_1") (pintype "passive"))
      (node (ref "U4") (pin "56") (pinfunction "BAUD1_56") (pintype "passive"))
    )
    (net (code "65") (name "Net-(U4-BAUD2)") (class "Default")
      (node (ref "R21") (pin "1") (pinfunction "1_1") (pintype "passive"))
      (node (ref "U4") (pin "55") (pinfunction "BAUD2_55") (pintype "passive"))
    )
    (net (code "66") (name "Net-(U4-RREF)") (class "Default")
      (node (ref "R19") (pin "2") (pinfunction "2_2") (pintype "passive"))
      (node (ref "U4") (pin "3") (pinfunction "RREF_3") (pintype "passive"))
    )
    (net (code "67") (name "Net-(U4-VCM)") (class "Default")
      (node (ref "C47") (pin "1") (pinfunction "1_1") (pintype "passive"))
      (node (ref "U4") (pin "11") (pinfunction "VCM_11") (pintype "passive"))
    )
    (net (code "68") (name "Net-(U4-VREF)") (class "Default")
      (node (ref "C26") (pin "2") (pinfunction "2_2") (pintype "passive"))
      (node (ref "U4") (pin "18") (pinfunction "VREF_18") (pintype "passive"))
    )
    (net (code "69") (name "Net-(U4-XTALI)") (class "Default")
      (node (ref "C54") (pin "2") (pinfunction "2_2") (pintype "passive"))
      (node (ref "U4") (pin "26") (pinfunction "XTALI_26") (pintype "passive"))
      (node (ref "Y1") (pin "1") (pinfunction "1_1") (pintype "passive"))
    )
    (net (code "70") (name "Net-(U4-XTALO)") (class "Default")
      (node (ref "C57") (pin "2") (pinfunction "2_2") (pintype "passive"))
      (node (ref "U4") (pin "27") (pinfunction "XTALO_27") (pintype "passive"))
      (node (ref "Y1") (pin "2") (pinfunction "2_2") (pintype "passive"))
    )
    (net (code "71") (name "Net-(U5-AVDD)") (class "Default")
      (node (ref "C34") (pin "2") (pinfunction "2_2") (pintype "passive"))
      (node (ref "U5") (pin "3") (pinfunction "AVDD_3") (pintype "passive"))
      (node (ref "U5") (pin "4") (pinfunction "VREF_4") (pintype "passive"))
      (node (ref "U5") (pin "5") (pinfunction "VOLUME_5") (pintype "passive"))
    )
    (net (code "72") (name "Net-(U5-BSLN)") (class "Default")
      (node (ref "C55") (pin "1") (pinfunction "1_1") (pintype "passive"))
      (node (ref "U5") (pin "15") (pinfunction "BSLN_15") (pintype "passive"))
    )
    (net (code "73") (name "Net-(U5-BSLP)") (class "Default")
      (node (ref "C56") (pin "1") (pinfunction "1_1") (pintype "passive"))
      (node (ref "U5") (pin "16") (pinfunction "BSLP_16") (pintype "passive"))
    )
    (net (code "74") (name "Net-(U5-BSRN)") (class "Default")
      (node (ref "C15") (pin "2") (pinfunction "2_2") (pintype "passive"))
      (node (ref "U5") (pin "36") (pinfunction "BSRN_36") (pintype "passive"))
    )
    (net (code "75") (name "Net-(U5-BSRP)") (class "Default")
      (node (ref "C16") (pin "1") (pinfunction "1_1") (pintype "passive"))
      (node (ref "U5") (pin "35") (pinfunction "BSRP_35") (pintype "passive"))
    )
    (net (code "76") (name "Net-(U5-COSC)") (class "Default")
      (node (ref "C42") (pin "1") (pinfunction "1_1") (pintype "passive"))
      (node (ref "U5") (pin "22") (pinfunction "COSC_22") (pintype "passive"))
    )
    (net (code "77") (name "Net-(U5-LINN)") (class "Default")
      (node (ref "C44") (pin "2") (pinfunction "2_2") (pintype "passive"))
      (node (ref "U5") (pin "10") (pinfunction "LINN_10") (pintype "passive"))
    )
    (net (code "78") (name "Net-(U5-LINP)") (class "Default")
      (node (ref "C41") (pin "2") (pinfunction "2_2") (pintype "passive"))
      (node (ref "U5") (pin "9") (pinfunction "LINP_9") (pintype "passive"))
    )
    (net (code "79") (name "Net-(U5-RINN)") (class "Default")
      (node (ref "C29") (pin "2") (pinfunction "2_2") (pintype "passive"))
      (node (ref "U5") (pin "1") (pinfunction "RINN_1") (pintype "passive"))
    )
    (net (code "80") (name "Net-(U5-RINP)") (class "Default")
      (node (ref "C32") (pin "2") (pinfunction "2_2") (pintype "passive"))
      (node (ref "U5") (pin "2") (pinfunction "RINP_2") (pintype "passive"))
    )
    (net (code "81") (name "Net-(U5-ROSC)") (class "Default")
      (node (ref "R18") (pin "2") (pinfunction "2_2") (pintype "passive"))
      (node (ref "U5") (pin "23") (pinfunction "ROSC_23") (pintype "passive"))
    )
    (net (code "82") (name "Net-(U5-V2P5)") (class "Default")
      (node (ref "C35") (pin "1") (pinfunction "1_1") (pintype "passive"))
      (node (ref "U5") (pin "27") (pinfunction "V2P5_27") (pintype "passive"))
    )
    (net (code "83") (name "Net-(U5-VCLAMPL)") (class "Default")
      (node (ref "C45") (pin "1") (pinfunction "1_1") (pintype "passive"))
      (node (ref "U5") (pin "21") (pinfunction "VCLAMPL_21") (pintype "passive"))
    )
    (net (code "84") (name "Net-(U5-VCLAMPR)") (class "Default")
      (node (ref "C30") (pin "1") (pinfunction "1_1") (pintype "passive"))
      (node (ref "U5") (pin "30") (pinfunction "VCLAMPR_30") (pintype "passive"))
    )
    (net (code "85") (name "VCC3.3") (class "Default")
      (node (ref "C4") (pin "2") (pinfunction "2_2") (pintype "passive"))
      (node (ref "C48") (pin "1") (pinfunction "1_1") (pintype "passive"))
      (node (ref "C49") (pin "1") (pinfunction "1_1") (pintype "passive"))
      (node (ref "C8") (pin "2") (pinfunction "2_2") (pintype "passive"))
      (node (ref "L2") (pin "2") (pinfunction "2_2") (pintype "passive"))
      (node (ref "R26") (pin "1") (pinfunction "1_1") (pintype "passive"))
      (node (ref "R5") (pin "1") (pinfunction "1_1") (pintype "passive"))
      (node (ref "R7") (pin "2") (pintype "passive"))
      (node (ref "U1") (pin "16") (pinfunction "VCC_16") (pintype "passive"))
      (node (ref "U4") (pin "20") (pinfunction "PWR_IN_20") (pintype "passive"))
    )
    (net (code "86") (name "VCC12") (class "Default")
      (node (ref "C6") (pin "2") (pinfunction "2_2") (pintype "passive"))
      (node (ref "D6") (pin "2") (pinfunction "A_2") (pintype "passive"))
      (node (ref "D7") (pin "2") (pinfunction "A_2") (pintype "passive"))
      (node (ref "L1") (pin "2") (pinfunction "2_2") (pintype "passive"))
      (node (ref "R4") (pin "2") (pinfunction "2_2") (pintype "passive"))
      (node (ref "R6") (pin "2") (pintype "passive"))
    )
    (net (code "87") (name "VCC24") (class "Default")
      (node (ref "C5") (pin "1") (pinfunction "1_1") (pintype "passive"))
      (node (ref "C7") (pin "1") (pinfunction "1_1") (pintype "passive"))
      (node (ref "F1") (pin "2") (pinfunction "2_2") (pintype "passive"))
      (node (ref "R1") (pin "1") (pintype "passive"))
      (node (ref "R2") (pin "1") (pintype "passive"))
      (node (ref "R3") (pin "1") (pinfunction "1_1") (pintype "passive"))
      (node (ref "U2") (pin "7") (pinfunction "VIN_7") (pintype "passive"))
      (node (ref "U3") (pin "7") (pinfunction "VIN_7") (pintype "passive"))
    )
    (net (code "88") (name "VDD12") (class "Default")
      (node (ref "C21") (pin "1") (pinfunction "1_1") (pintype "passive"))
      (node (ref "C36") (pin "1") (pinfunction "1_1") (pintype "passive"))
      (node (ref "C37") (pin "1") (pinfunction "1_1") (pintype "passive"))
      (node (ref "U4") (pin "1") (pinfunction "VDD12_1") (pintype "passive"))
      (node (ref "U4") (pin "23") (pinfunction "VDD12_O_23") (pintype "passive"))
    )
    (net (code "89") (name "VDD33") (class "Default")
      (node (ref "C19") (pin "1") (pinfunction "1_1") (pintype "passive"))
      (node (ref "C20") (pin "1") (pinfunction "1_1") (pintype "passive"))
      (node (ref "C27") (pin "1") (pinfunction "1_1") (pintype "passive"))
      (node (ref "C28") (pin "1") (pinfunction "1_1") (pintype "passive"))
      (node (ref "FB3") (pin "2") (pinfunction "2_2") (pintype "passive"))
      (node (ref "R16") (pin "2") (pinfunction "2_2") (pintype "passive"))
      (node (ref "R17") (pin "1") (pinfunction "1_1") (pintype "passive"))
      (node (ref "R21") (pin "2") (pinfunction "2_2") (pintype "passive"))
      (node (ref "R22") (pin "2") (pinfunction "2_2") (pintype "passive"))
      (node (ref "R24") (pin "1") (pinfunction "1_1") (pintype "passive"))
      (node (ref "R25") (pin "1") (pinfunction "1_1") (pintype "passive"))
      (node (ref "U4") (pin "22") (pinfunction "VDD33_O_22") (pintype "passive"))
      (node (ref "U4") (pin "36") (pinfunction "VDD33_36") (pintype "passive"))
      (node (ref "U4") (pin "46") (pinfunction "VDD33_46") (pintype "passive"))
    )
    (net (code "90") (name "unconnected-(U1-DIN2-Pad10)") (class "Default")
      (node (ref "U1") (pin "10") (pinfunction "DIN2_10") (pintype "passive"))
    )
    (net (code "91") (name "unconnected-(U1-DOUT2-Pad7)") (class "Default")
      (node (ref "U1") (pin "7") (pinfunction "DOUT2_7") (pintype "passive"))
    )
    (net (code "92") (name "unconnected-(U1-RIN2-Pad8)") (class "Default")
      (node (ref "U1") (pin "8") (pinfunction "RIN2_8") (pintype "passive"))
    )
    (net (code "93") (name "unconnected-(U1-ROUT2-Pad9)") (class "Default")
      (node (ref "U1") (pin "9") (pinfunction "ROUT2_9") (pintype "passive"))
    )
    (net (code "94") (name "unconnected-(U4-NC-Pad5)") (class "Default")
      (node (ref "U4") (pin "5") (pinfunction "NC_5") (pintype "passive"))
    )
    (net (code "95") (name "unconnected-(U4-NC-Pad6)") (class "Default")
      (node (ref "U4") (pin "6") (pinfunction "NC_6") (pintype "passive"))
    )
    (net (code "96") (name "unconnected-(U4-NC-Pad19)") (class "Default")
      (node (ref "U4") (pin "19") (pinfunction "NC_19") (pintype "passive"))
    )
    (net (code "97") (name "unconnected-(U4-NC-Pad30)") (class "Default")
      (node (ref "U4") (pin "30") (pinfunction "NC_30") (pintype "passive"))
    )
    (net (code "98") (name "unconnected-(U4-NC-Pad31)") (class "Default")
      (node (ref "U4") (pin "31") (pinfunction "NC_31") (pintype "passive"))
    )
    (net (code "99") (name "unconnected-(U4-NC-Pad32)") (class "Default")
      (node (ref "U4") (pin "32") (pinfunction "NC_32") (pintype "passive"))
    )
    (net (code "100") (name "unconnected-(U4-NC-Pad33)") (class "Default")
      (node (ref "U4") (pin "33") (pinfunction "NC_33") (pintype "passive"))
    )
    (net (code "101") (name "unconnected-(U4-NC-Pad34)") (class "Default")
      (node (ref "U4") (pin "34") (pinfunction "NC_34") (pintype "passive"))
    )
    (net (code "102") (name "unconnected-(U4-NC-Pad35)") (class "Default")
      (node (ref "U4") (pin "35") (pinfunction "NC_35") (pintype "passive"))
    )
    (net (code "103") (name "unconnected-(U4-NC-Pad38)") (class "Default")
      (node (ref "U4") (pin "38") (pinfunction "NC_38") (pintype "passive"))
    )
    (net (code "104") (name "unconnected-(U4-NC-Pad58)") (class "Default")
      (node (ref "U4") (pin "58") (pinfunction "NC_58") (pintype "passive"))
    )
    (net (code "105") (name "unconnected-(U4-NC-Pad61)") (class "Default")
      (node (ref "U4") (pin "61") (pinfunction "NC_61") (pintype "passive"))
    )
    (net (code "106") (name "unconnected-(U4-NC-Pad63)") (class "Default")
      (node (ref "U4") (pin "63") (pinfunction "NC_63") (pintype "passive"))
    )
  )
)
